# 11_DAC.net
KiCad netlist of a schematic drawn in Altium Designer
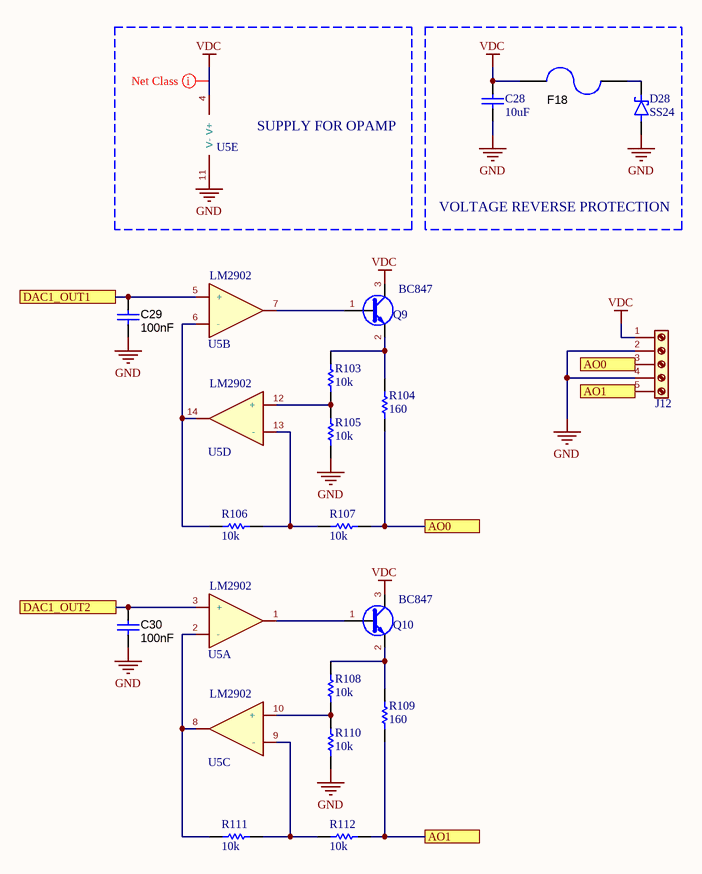
[diagram p0: 11_DAC.SchDoc]

(export (version "E")
  (design (tool "Eeschema 10.0.6"))
  (components
    (comp (ref "C28")
      (value "CGA6P1X7R1E106M250AC")
      (footprint "C_1206_3216Metric")
      (fields
        (field (name "MANUFACTURER") "TDK")
        (field (name "VALUEDISPLAYED") "10uF")
        (field (name "PUBLISHER") "Texas Instruments")
      )
      (libsource (lib "PROC051C_AWR1843BOOST_RevC") (part "CAP 10uF 1206"))
    )
    (comp (ref "C29")
      (value "CAP 100nF 0603")
      (footprint "0603")
      (description "CAP, CERM, 100 nF, 25 V, +/- 10%, X7R, AEC-Q200 Grade 1, 0603")
      (fields
        (field (name "MANUFACTURER") "MuRata")
        (field (name "PARTNUMBER") "GCM188R70J225KE22D")
        (field (name "VALUEDISPLAYED") "100nF")
        (field (name "PUBLISHER") "Texas Instruments")
      )
      (libsource (lib "PROC051C_AWR1843BOOST_RevC") (part "CAP 100nF 0603"))
    )
    (comp (ref "C30")
      (value "CAP 100nF 0603")
      (footprint "0603")
      (description "CAP, CERM, 100 nF, 25 V, +/- 10%, X7R, AEC-Q200 Grade 1, 0603")
      (fields
        (field (name "MANUFACTURER") "MuRata")
        (field (name "PARTNUMBER") "GCM188R70J225KE22D")
        (field (name "VALUEDISPLAYED") "100nF")
        (field (name "PUBLISHER") "Texas Instruments")
      )
      (libsource (lib "PROC051C_AWR1843BOOST_RevC") (part "CAP 100nF 0603"))
    )
    (comp (ref "D28")
      (value "SS24")
      (footprint "DIOM5336X265N")
      (description "Diode Schottky 40V 2A Surface Mount DO-214AA (SMB)")
      (fields (field (name "MF") "ON Semiconductor"))
      (libsource (lib "PROC051C_AWR1843BOOST_RevC") (part "SS24"))
    )
    (comp (ref "F18")
      (value "0440005.WR")
      (footprint "CAPC4520X203N")
      (description "Fuse, 5 A, 32VAC/VDC, SMD")
      (fields (field (name "MANUFACTURER") "Littelfuse"))
      (libsource (lib "PROC051C_AWR1843BOOST_RevC") (part "FUSE 1808"))
    )
    (comp (ref "J12")
      (value "Terminal_01x5_P5.00")
      (footprint "TerminalBlock_Phoenix_PT-1,5-5-5.0-H_1x5_P5.00mm_Horizontal")
      (libsource (lib "PROC051C_AWR1843BOOST_RevC") (part "Terminal_01x5_P5.00"))
    )
    (comp (ref "Q9")
      (value "BC847")
      (footprint "SOT-23")
      (libsource (lib "PROC051C_AWR1843BOOST_RevC") (part "BC847"))
    )
    (comp (ref "Q10")
      (value "BC847")
      (footprint "SOT-23")
      (libsource (lib "PROC051C_AWR1843BOOST_RevC") (part "BC847"))
    )
    (comp (ref "R103")
      (value "RES 10K 0603")
      (footprint "0603")
      (description "RES, 10K, 1%, 0.1 W, AEC-Q200 Grade 0, 0603")
      (fields
        (field (name "MANUFACTURER") "Vishay-Dale")
        (field (name "PARTNUMBER") "CRCW060320R0JNEA")
        (field (name "VALUEDISPLAYED") "10k")
      )
      (libsource (lib "PROC051C_AWR1843BOOST_RevC") (part "RES 10K 0603 1%"))
    )
    (comp (ref "R104")
      (value "CRCW060320R0JNEA")
      (footprint "0603")
      (description "RES, 160, 5%, 0.1 W, AEC-Q200 Grade 0, 0603")
      (fields (field (name "MANUFACTURER") "Vishay-Dale") (field (name "VALUEDISPLAYED") "160"))
      (libsource (lib "PROC051C_AWR1843BOOST_RevC") (part "RES 160R 0603"))
    )
    (comp (ref "R105")
      (value "RES 10K 0603")
      (footprint "0603")
      (description "RES, 10K, 1%, 0.1 W, AEC-Q200 Grade 0, 0603")
      (fields
        (field (name "MANUFACTURER") "Vishay-Dale")
        (field (name "PARTNUMBER") "CRCW060320R0JNEA")
        (field (name "VALUEDISPLAYED") "10k")
      )
      (libsource (lib "PROC051C_AWR1843BOOST_RevC") (part "RES 10K 0603 1%"))
    )
    (comp (ref "R106")
      (value "RES 10K 0603")
      (footprint "0603")
      (description "RES, 10K, 1%, 0.1 W, AEC-Q200 Grade 0, 0603")
      (fields
        (field (name "MANUFACTURER") "Vishay-Dale")
        (field (name "PARTNUMBER") "CRCW060320R0JNEA")
        (field (name "VALUEDISPLAYED") "10k")
      )
      (libsource (lib "PROC051C_AWR1843BOOST_RevC") (part "RES 10K 0603 1%"))
    )
    (comp (ref "R107")
      (value "RES 10K 0603")
      (footprint "0603")
      (description "RES, 10K, 1%, 0.1 W, AEC-Q200 Grade 0, 0603")
      (fields
        (field (name "MANUFACTURER") "Vishay-Dale")
        (field (name "PARTNUMBER") "CRCW060320R0JNEA")
        (field (name "VALUEDISPLAYED") "10k")
      )
      (libsource (lib "PROC051C_AWR1843BOOST_RevC") (part "RES 10K 0603 1%"))
    )
    (comp (ref "R108")
      (value "RES 10K 0603")
      (footprint "0603")
      (description "RES, 10K, 1%, 0.1 W, AEC-Q200 Grade 0, 0603")
      (fields
        (field (name "MANUFACTURER") "Vishay-Dale")
        (field (name "PARTNUMBER") "CRCW060320R0JNEA")
        (field (name "VALUEDISPLAYED") "10k")
      )
      (libsource (lib "PROC051C_AWR1843BOOST_RevC") (part "RES 10K 0603 1%"))
    )
    (comp (ref "R109")
      (value "CRCW060320R0JNEA")
      (footprint "0603")
      (description "RES, 160, 5%, 0.1 W, AEC-Q200 Grade 0, 0603")
      (fields (field (name "MANUFACTURER") "Vishay-Dale") (field (name "VALUEDISPLAYED") "160"))
      (libsource (lib "PROC051C_AWR1843BOOST_RevC") (part "RES 160R 0603"))
    )
    (comp (ref "R110")
      (value "RES 10K 0603")
      (footprint "0603")
      (description "RES, 10K, 1%, 0.1 W, AEC-Q200 Grade 0, 0603")
      (fields
        (field (name "MANUFACTURER") "Vishay-Dale")
        (field (name "PARTNUMBER") "CRCW060320R0JNEA")
        (field (name "VALUEDISPLAYED") "10k")
      )
      (libsource (lib "PROC051C_AWR1843BOOST_RevC") (part "RES 10K 0603 1%"))
    )
    (comp (ref "R111")
      (value "RES 10K 0603")
      (footprint "0603")
      (description "RES, 10K, 1%, 0.1 W, AEC-Q200 Grade 0, 0603")
      (fields
        (field (name "MANUFACTURER") "Vishay-Dale")
        (field (name "PARTNUMBER") "CRCW060320R0JNEA")
        (field (name "VALUEDISPLAYED") "10k")
      )
      (libsource (lib "PROC051C_AWR1843BOOST_RevC") (part "RES 10K 0603 1%"))
    )
    (comp (ref "R112")
      (value "RES 10K 0603")
      (footprint "0603")
      (description "RES, 10K, 1%, 0.1 W, AEC-Q200 Grade 0, 0603")
      (fields
        (field (name "MANUFACTURER") "Vishay-Dale")
        (field (name "PARTNUMBER") "CRCW060320R0JNEA")
        (field (name "VALUEDISPLAYED") "10k")
      )
      (libsource (lib "PROC051C_AWR1843BOOST_RevC") (part "RES 10K 0603 1%"))
    )
    (comp (ref "U5")
      (value "LM2902")
      (footprint "SOIC-14_3.9x8.7mm_P1.27mm")
      (libsource (lib "PROC051C_AWR1843BOOST_RevC") (part "LM2902"))
    )
  )
  (nets
    (net (code "1") (name "/AO0") (class "Default")
      (node (ref "J12") (pin "3") (pinfunction "Pin_3_3") (pintype "passive"))
      (node (ref "R104") (pin "1") (pinfunction "1_1") (pintype "passive"))
      (node (ref "R107") (pin "2") (pinfunction "2_2") (pintype "passive"))
    )
    (net (code "2") (name "/AO1") (class "Default")
      (node (ref "J12") (pin "5") (pinfunction "Pin_5_5") (pintype "passive"))
      (node (ref "R109") (pin "1") (pinfunction "1_1") (pintype "passive"))
      (node (ref "R112") (pin "2") (pinfunction "2_2") (pintype "passive"))
    )
    (net (code "3") (name "/DAC1_OUT1") (class "Default")
      (node (ref "C29") (pin "1") (pinfunction "1_1") (pintype "passive"))
      (node (ref "U5") (pin "5") (pinfunction "+_5") (pintype "passive"))
    )
    (net (code "4") (name "/DAC1_OUT2") (class "Default")
      (node (ref "C30") (pin "1") (pinfunction "1_1") (pintype "passive"))
      (node (ref "U5") (pin "3") (pinfunction "+_3") (pintype "passive"))
    )
    (net (code "5") (name "GND") (class "Default")
      (node (ref "C28") (pin "2") (pinfunction "2_2") (pintype "passive"))
      (node (ref "C29") (pin "2") (pinfunction "2_2") (pintype "passive"))
      (node (ref "C30") (pin "2") (pinfunction "2_2") (pintype "passive"))
      (node (ref "D28") (pin "A") (pinfunction "A_A") (pintype "passive"))
      (node (ref "J12") (pin "2") (pinfunction "Pin_2_2") (pintype "passive"))
      (node (ref "J12") (pin "4") (pinfunction "Pin_4_4") (pintype "passive"))
      (node (ref "R105") (pin "1") (pinfunction "1_1") (pintype "passive"))
      (node (ref "R110") (pin "1") (pinfunction "1_1") (pintype "passive"))
      (node (ref "U5") (pin "11") (pinfunction "V-_11") (pintype "passive"))
    )
    (net (code "6") (name "Net-(D28-K)") (class "Default")
      (node (ref "D28") (pin "C") (pinfunction "K_C") (pintype "passive"))
      (node (ref "F18") (pin "1") (pinfunction "1_1") (pintype "passive"))
    )
    (net (code "7") (name "Net-(Q9-B)") (class "Default")
      (node (ref "Q9") (pin "1") (pinfunction "B_1") (pintype "passive"))
      (node (ref "U5") (pin "7") (pinfunction "7_7") (pintype "passive"))
    )
    (net (code "8") (name "Net-(Q9-E)") (class "Default")
      (node (ref "Q9") (pin "2") (pinfunction "E_2") (pintype "passive"))
      (node (ref "R103") (pin "2") (pinfunction "2_2") (pintype "passive"))
      (node (ref "R104") (pin "2") (pinfunction "2_2") (pintype "passive"))
    )
    (net (code "9") (name "Net-(Q10-B)") (class "Default")
      (node (ref "Q10") (pin "1") (pinfunction "B_1") (pintype "passive"))
      (node (ref "U5") (pin "1") (pinfunction "1_1") (pintype "passive"))
    )
    (net (code "10") (name "Net-(Q10-E)") (class "Default")
      (node (ref "Q10") (pin "2") (pinfunction "E_2") (pintype "passive"))
      (node (ref "R108") (pin "2") (pinfunction "2_2") (pintype "passive"))
      (node (ref "R109") (pin "2") (pinfunction "2_2") (pintype "passive"))
    )
    (net (code "11") (name "Net-(U5A--)") (class "Default")
      (node (ref "R111") (pin "1") (pinfunction "1_1") (pintype "passive"))
      (node (ref "U5") (pin "2") (pinfunction "-_2") (pintype "passive"))
      (node (ref "U5") (pin "8") (pinfunction "8_8") (pintype "passive"))
    )
    (net (code "12") (name "Net-(U5B--)") (class "Default")
      (node (ref "R106") (pin "1") (pinfunction "1_1") (pintype "passive"))
      (node (ref "U5") (pin "14") (pinfunction "14_14") (pintype "passive"))
      (node (ref "U5") (pin "6") (pinfunction "-_6") (pintype "passive"))
    )
    (net (code "13") (name "Net-(U5C-+)") (class "Default")
      (node (ref "R108") (pin "1") (pinfunction "1_1") (pintype "passive"))
      (node (ref "R110") (pin "2") (pinfunction "2_2") (pintype "passive"))
      (node (ref "U5") (pin "10") (pinfunction "+_10") (pintype "passive"))
    )
    (net (code "14") (name "Net-(U5C--)") (class "Default")
      (node (ref "R111") (pin "2") (pinfunction "2_2") (pintype "passive"))
      (node (ref "R112") (pin "1") (pinfunction "1_1") (pintype "passive"))
      (node (ref "U5") (pin "9") (pinfunction "-_9") (pintype "passive"))
    )
    (net (code "15") (name "Net-(U5D-+)") (class "Default")
      (node (ref "R103") (pin "1") (pinfunction "1_1") (pintype "passive"))
      (node (ref "R105") (pin "2") (pinfunction "2_2") (pintype "passive"))
      (node (ref "U5") (pin "12") (pinfunction "+_12") (pintype "passive"))
    )
    (net (code "16") (name "Net-(U5D--)") (class "Default")
      (node (ref "R106") (pin "2") (pinfunction "2_2") (pintype "passive"))
      (node (ref "R107") (pin "1") (pinfunction "1_1") (pintype "passive"))
      (node (ref "U5") (pin "13") (pinfunction "-_13") (pintype "passive"))
    )
    (net (code "17") (name "VDC") (class "Default")
      (node (ref "C28") (pin "1") (pinfunction "1_1") (pintype "passive"))
      (node (ref "F18") (pin "2") (pinfunction "2_2") (pintype "passive"))
      (node (ref "J12") (pin "1") (pinfunction "Pin_1_1") (pintype "passive"))
      (node (ref "Q10") (pin "3") (pinfunction "C_3") (pintype "passive"))
      (node (ref "Q9") (pin "3") (pinfunction "C_3") (pintype "passive"))
      (node (ref "U5") (pin "4") (pinfunction "V+_4") (pintype "passive"))
    )
  )
)
